# PEDALBOX_BULKHEAD.net
KiCad netlist of a schematic drawn in Altium Designer
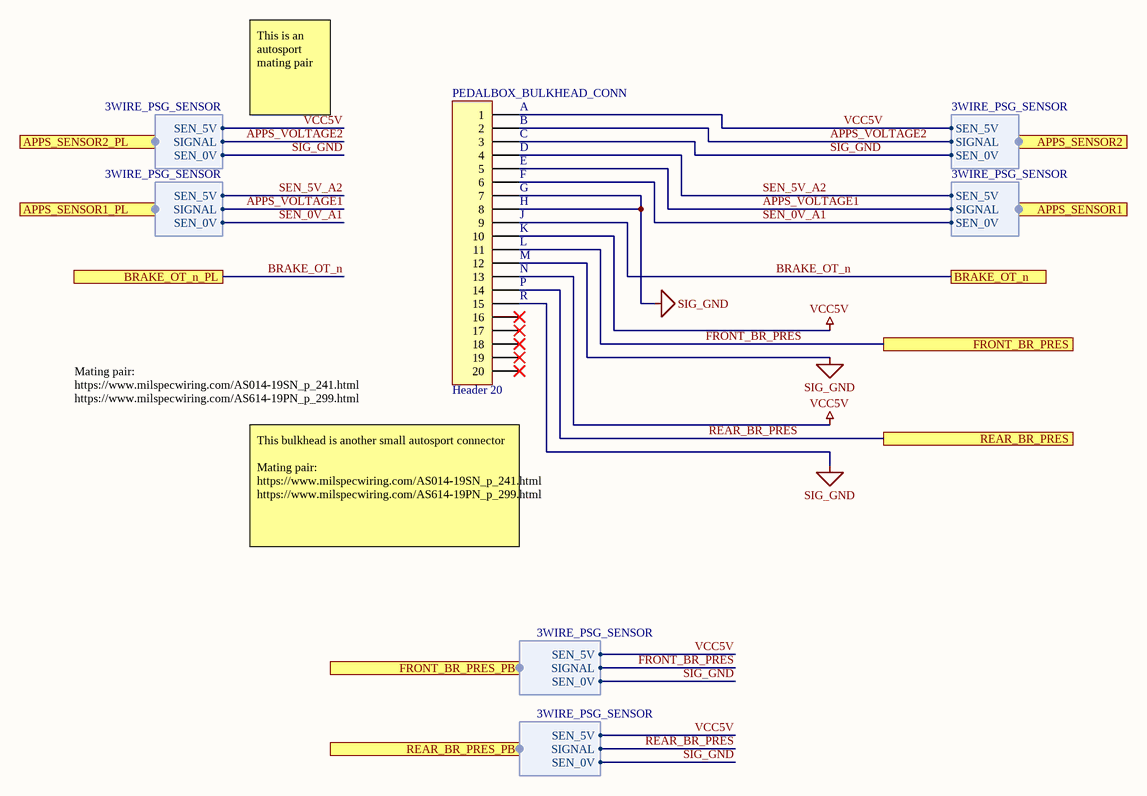
[diagram p0: PEDALBOX_BULKHEAD.SchDoc]

(export (version "E")
  (design (tool "Eeschema 10.0.6"))
  (components
    (comp (ref "PEDALBOX_BULKHEAD_CONN")
      (value "Header 20")
      (footprint "HDR1X20")
      (description "Header, 20-Pin")
      (fields (field (name "PUBLISHER") "Altium Limited"))
      (libsource (lib "Miscellaneous Connectors") (part "Header 20"))
    )
  )
  (nets
    (net (code "2") (name "/APPS_VOLTAGE1") (class "Default")
      (node (ref "PEDALBOX_BULKHEAD_CONN") (pin "5") (pinfunction "5_5") (pintype "passive"))
    )
    (net (code "3") (name "/APPS_VOLTAGE2") (class "Default")
      (node (ref "PEDALBOX_BULKHEAD_CONN") (pin "2") (pinfunction "2_2") (pintype "passive"))
    )
    (net (code "4") (name "/BRAKE_OT_n") (class "Default")
      (node (ref "PEDALBOX_BULKHEAD_CONN") (pin "9") (pinfunction "9_9") (pintype "passive"))
    )
    (net (code "5") (name "/FRONT_BR_PRES") (class "Default")
      (node (ref "PEDALBOX_BULKHEAD_CONN") (pin "11") (pinfunction "11_11") (pintype "passive"))
    )
    (net (code "6") (name "/REAR_BR_PRES") (class "Default")
      (node (ref "PEDALBOX_BULKHEAD_CONN") (pin "14") (pinfunction "14_14") (pintype "passive"))
    )
    (net (code "7") (name "/SEN_0V_A1") (class "Default")
      (node (ref "PEDALBOX_BULKHEAD_CONN") (pin "6") (pinfunction "6_6") (pintype "passive"))
    )
    (net (code "8") (name "/SEN_5V_A2") (class "Default")
      (node (ref "PEDALBOX_BULKHEAD_CONN") (pin "4") (pinfunction "4_4") (pintype "passive"))
    )
    (net (code "10") (name "SIG_GND") (class "Default")
      (node (ref "PEDALBOX_BULKHEAD_CONN") (pin "12") (pinfunction "12_12") (pintype "passive"))
      (node (ref "PEDALBOX_BULKHEAD_CONN") (pin "15") (pinfunction "15_15") (pintype "passive"))
      (node (ref "PEDALBOX_BULKHEAD_CONN") (pin "3") (pinfunction "3_3") (pintype "passive"))
      (node (ref "PEDALBOX_BULKHEAD_CONN") (pin "7") (pinfunction "7_7") (pintype "passive"))
      (node (ref "PEDALBOX_BULKHEAD_CONN") (pin "8") (pinfunction "8_8") (pintype "passive"))
    )
    (net (code "11") (name "VCC5V") (class "Default")
      (node (ref "PEDALBOX_BULKHEAD_CONN") (pin "1") (pinfunction "1_1") (pintype "passive"))
      (node (ref "PEDALBOX_BULKHEAD_CONN") (pin "10") (pinfunction "10_10") (pintype "passive"))
      (node (ref "PEDALBOX_BULKHEAD_CONN") (pin "13") (pinfunction "13_13") (pintype "passive"))
    )
    (net (code "12") (name "unconnected-(PEDALBOX_BULKHEAD_CONN-Pad16)") (class "Default")
      (node (ref "PEDALBOX_BULKHEAD_CONN") (pin "16") (pinfunction "16_16") (pintype "passive+no_connect"))
    )
    (net (code "13") (name "unconnected-(PEDALBOX_BULKHEAD_CONN-Pad17)") (class "Default")
      (node (ref "PEDALBOX_BULKHEAD_CONN") (pin "17") (pinfunction "17_17") (pintype "passive+no_connect"))
    )
    (net (code "14") (name "unconnected-(PEDALBOX_BULKHEAD_CONN-Pad18)") (class "Default")
      (node (ref "PEDALBOX_BULKHEAD_CONN") (pin "18") (pinfunction "18_18") (pintype "passive+no_connect"))
    )
    (net (code "15") (name "unconnected-(PEDALBOX_BULKHEAD_CONN-Pad19)") (class "Default")
      (node (ref "PEDALBOX_BULKHEAD_CONN") (pin "19") (pinfunction "19_19") (pintype "passive+no_connect"))
    )
    (net (code "16") (name "unconnected-(PEDALBOX_BULKHEAD_CONN-Pad20)") (class "Default")
      (node (ref "PEDALBOX_BULKHEAD_CONN") (pin "20") (pinfunction "20_20") (pintype "passive+no_connect"))
    )
  )
)
